# sub_board.net
KiCad netlist of a schematic drawn in EAGLE
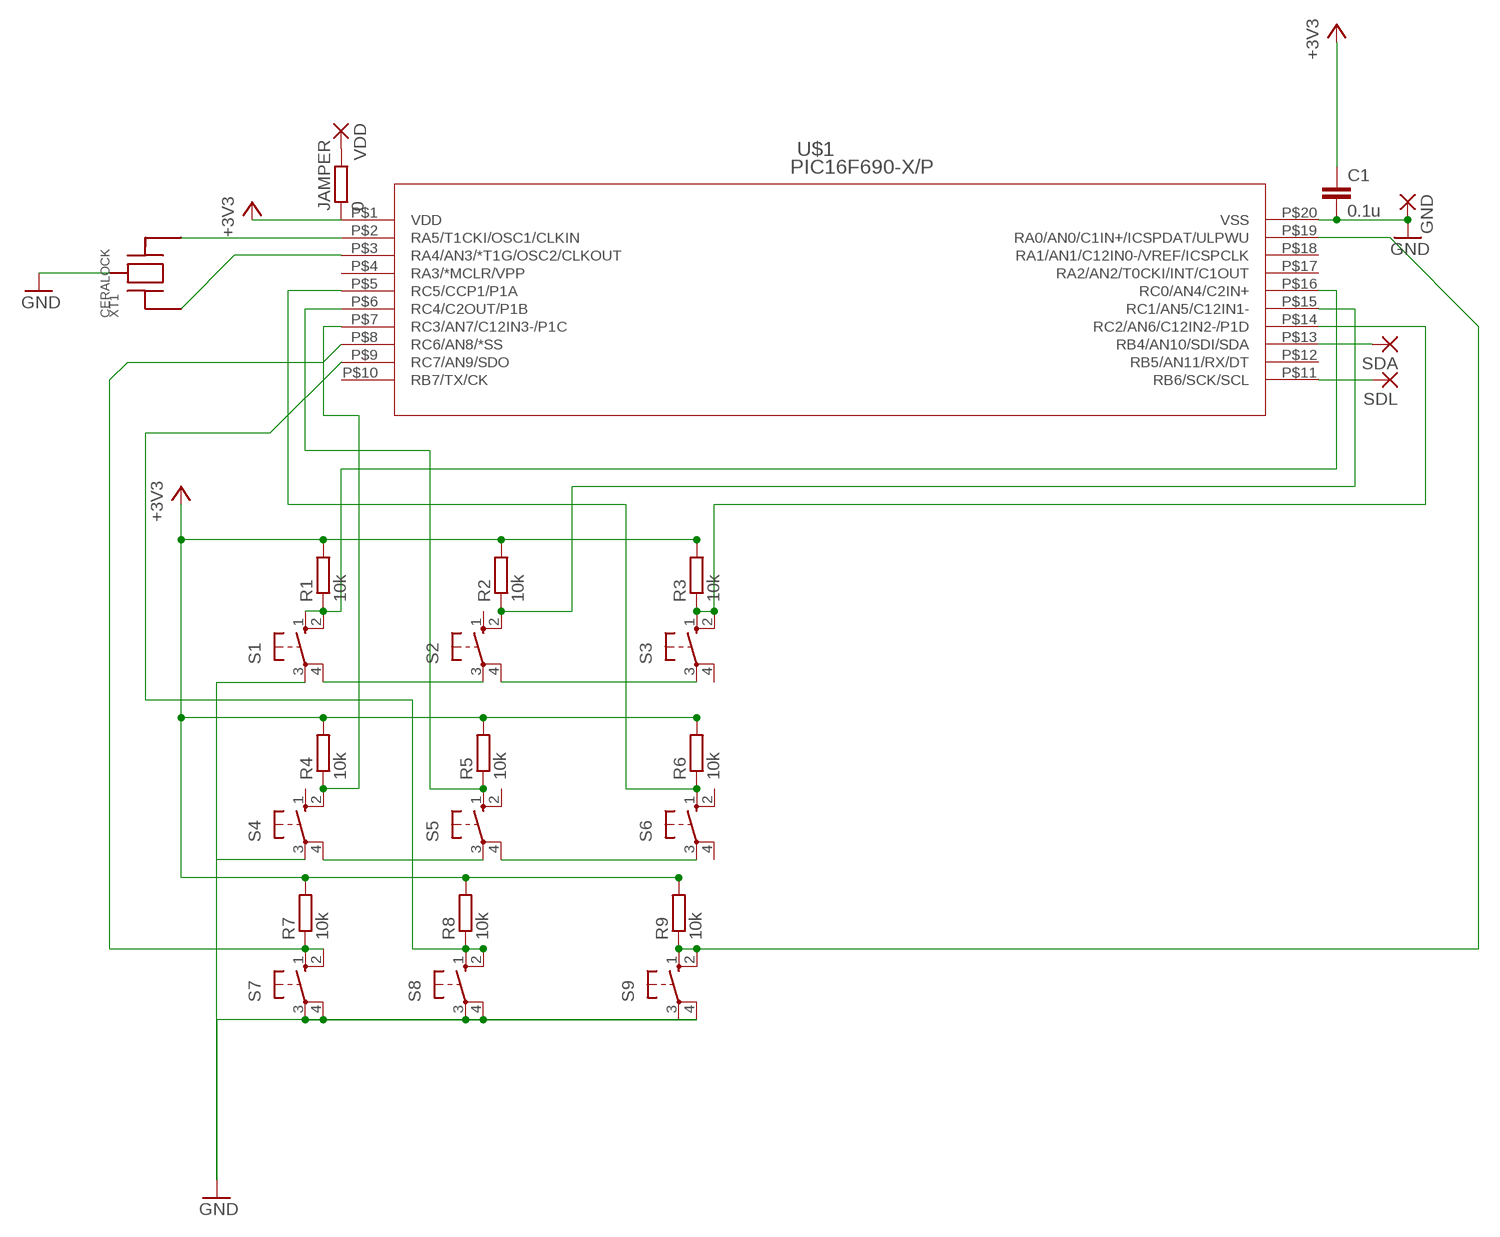
[diagram p0: schematic, sheet 1]

(export (version "E")
  (design (tool "Eeschema 10.0.6"))
  (components
    (comp (ref "C1")
      (value "0.1u")
      (footprint "eagle-import:C025-024X044")
      (libsource (lib "eagle-import") (part "C-EU025-024X044"))
    )
    (comp (ref "GND")
      (value "2,15/1,0")
      (footprint "eagle-import:2,15_1,0")
      (libsource (lib "eagle-import") (part "2,15/1,0"))
    )
    (comp (ref "JAMPER")
      (value "0")
      (footprint "eagle-import:0207_10")
      (libsource (lib "eagle-import") (part "R-EU_0207/10"))
    )
    (comp (ref "R1")
      (value "10k")
      (footprint "eagle-import:0204_7")
      (libsource (lib "eagle-import") (part "R-EU_0204/7"))
    )
    (comp (ref "R2")
      (value "10k")
      (footprint "eagle-import:0204_7")
      (libsource (lib "eagle-import") (part "R-EU_0204/7"))
    )
    (comp (ref "R3")
      (value "10k")
      (footprint "eagle-import:0204_7")
      (libsource (lib "eagle-import") (part "R-EU_0204/7"))
    )
    (comp (ref "R4")
      (value "10k")
      (footprint "eagle-import:0204_7")
      (libsource (lib "eagle-import") (part "R-EU_0204/7"))
    )
    (comp (ref "R5")
      (value "10k")
      (footprint "eagle-import:0204_7")
      (libsource (lib "eagle-import") (part "R-EU_0204/7"))
    )
    (comp (ref "R6")
      (value "10k")
      (footprint "eagle-import:0204_7")
      (libsource (lib "eagle-import") (part "R-EU_0204/7"))
    )
    (comp (ref "R7")
      (value "10k")
      (footprint "eagle-import:0204_7")
      (libsource (lib "eagle-import") (part "R-EU_0204/7"))
    )
    (comp (ref "R8")
      (value "10k")
      (footprint "eagle-import:0204_7")
      (libsource (lib "eagle-import") (part "R-EU_0204/7"))
    )
    (comp (ref "R9")
      (value "10k")
      (footprint "eagle-import:0204_7")
      (libsource (lib "eagle-import") (part "R-EU_0204/7"))
    )
    (comp (ref "S1")
      (value "10-XX")
      (footprint "eagle-import:B3F-10XX")
      (fields (field (name "MPN") "B3F-1000"))
      (libsource (lib "eagle-import") (part "10-XX"))
    )
    (comp (ref "S2")
      (value "10-XX")
      (footprint "eagle-import:B3F-10XX")
      (fields (field (name "MPN") "B3F-1000"))
      (libsource (lib "eagle-import") (part "10-XX"))
    )
    (comp (ref "S3")
      (value "10-XX")
      (footprint "eagle-import:B3F-10XX")
      (fields (field (name "MPN") "B3F-1000"))
      (libsource (lib "eagle-import") (part "10-XX"))
    )
    (comp (ref "S4")
      (value "10-XX")
      (footprint "eagle-import:B3F-10XX")
      (fields (field (name "MPN") "B3F-1000"))
      (libsource (lib "eagle-import") (part "10-XX"))
    )
    (comp (ref "S5")
      (value "10-XX")
      (footprint "eagle-import:B3F-10XX")
      (fields (field (name "MPN") "B3F-1000"))
      (libsource (lib "eagle-import") (part "10-XX"))
    )
    (comp (ref "S6")
      (value "10-XX")
      (footprint "eagle-import:B3F-10XX")
      (fields (field (name "MPN") "B3F-1000"))
      (libsource (lib "eagle-import") (part "10-XX"))
    )
    (comp (ref "S7")
      (value "10-XX")
      (footprint "eagle-import:B3F-10XX")
      (fields (field (name "MPN") "B3F-1000"))
      (libsource (lib "eagle-import") (part "10-XX"))
    )
    (comp (ref "S8")
      (value "10-XX")
      (footprint "eagle-import:B3F-10XX")
      (fields (field (name "MPN") "B3F-1000"))
      (libsource (lib "eagle-import") (part "10-XX"))
    )
    (comp (ref "S9")
      (value "10-XX")
      (footprint "eagle-import:B3F-10XX")
      (fields (field (name "MPN") "B3F-1000"))
      (libsource (lib "eagle-import") (part "10-XX"))
    )
    (comp (ref "SDA")
      (value "2,15/1,0")
      (footprint "eagle-import:2,15_1,0")
      (libsource (lib "eagle-import") (part "2,15/1,0"))
    )
    (comp (ref "SDL")
      (value "2,15/1,0")
      (footprint "eagle-import:2,15_1,0")
      (libsource (lib "eagle-import") (part "2,15/1,0"))
    )
    (comp (ref "U$1")
      (value "PIC16F690-X/P")
      (footprint "eagle-import:PDIP20_300MC")
      (libsource (lib "eagle-import") (part "PIC16F690-X/P"))
    )
    (comp (ref "VDD")
      (value "2,15/1,0")
      (footprint "eagle-import:2,15_1,0")
      (libsource (lib "eagle-import") (part "2,15/1,0"))
    )
    (comp (ref "XT1")
      (value "CERALOCK")
      (footprint "eagle-import:CERALOCK")
      (libsource (lib "eagle-import") (part "CERALOCK"))
    )
  )
  (nets
    (net (code "1") (name "+3V3") (class "Default")
      (node (ref "C1") (pin "1") (pinfunction "1_1") (pintype "passive"))
      (node (ref "JAMPER") (pin "1") (pinfunction "1_1") (pintype "passive"))
      (node (ref "R1") (pin "2") (pinfunction "2_2") (pintype "passive"))
      (node (ref "R2") (pin "2") (pinfunction "2_2") (pintype "passive"))
      (node (ref "R3") (pin "2") (pinfunction "2_2") (pintype "passive"))
      (node (ref "R4") (pin "2") (pinfunction "2_2") (pintype "passive"))
      (node (ref "R5") (pin "2") (pinfunction "2_2") (pintype "passive"))
      (node (ref "R6") (pin "2") (pinfunction "2_2") (pintype "passive"))
      (node (ref "R7") (pin "2") (pinfunction "2_2") (pintype "passive"))
      (node (ref "R8") (pin "2") (pinfunction "2_2") (pintype "passive"))
      (node (ref "R9") (pin "2") (pinfunction "2_2") (pintype "passive"))
      (node (ref "U$1") (pin "P$1") (pinfunction "VDD_P$1") (pintype "passive"))
    )
    (net (code "2") (name "GND") (class "Default")
      (node (ref "C1") (pin "2") (pinfunction "2_2") (pintype "passive"))
      (node (ref "GND") (pin "1") (pinfunction "P_1") (pintype "passive"))
      (node (ref "S1") (pin "3") (pinfunction "P_3") (pintype "passive"))
      (node (ref "S4") (pin "3") (pinfunction "P_3") (pintype "passive"))
      (node (ref "S7") (pin "3") (pinfunction "P_3") (pintype "passive"))
      (node (ref "S7") (pin "4") (pinfunction "P1_4") (pintype "passive"))
      (node (ref "S8") (pin "3") (pinfunction "P_3") (pintype "passive"))
      (node (ref "S8") (pin "4") (pinfunction "P1_4") (pintype "passive"))
      (node (ref "S9") (pin "3") (pinfunction "P_3") (pintype "passive"))
      (node (ref "S9") (pin "4") (pinfunction "P1_4") (pintype "passive"))
      (node (ref "U$1") (pin "P$20") (pinfunction "VSS_P$20") (pintype "passive"))
      (node (ref "XT1") (pin "P$2") (pinfunction "2_P$2") (pintype "passive"))
    )
    (net (code "3") (name "Net-(S1-P1)") (class "Default")
      (node (ref "S1") (pin "4") (pinfunction "P1_4") (pintype "passive"))
      (node (ref "S2") (pin "3") (pinfunction "P_3") (pintype "passive"))
    )
    (net (code "4") (name "Net-(S1-S)") (class "Default")
      (node (ref "R1") (pin "1") (pinfunction "1_1") (pintype "passive"))
      (node (ref "S1") (pin "1") (pinfunction "S_1") (pintype "passive"))
      (node (ref "S1") (pin "2") (pinfunction "S1_2") (pintype "passive"))
      (node (ref "U$1") (pin "P$16") (pinfunction "RC0/AN4/C2IN+_P$16") (pintype "passive"))
    )
    (net (code "5") (name "Net-(S2-P1)") (class "Default")
      (node (ref "S2") (pin "4") (pinfunction "P1_4") (pintype "passive"))
      (node (ref "S3") (pin "3") (pinfunction "P_3") (pintype "passive"))
    )
    (net (code "6") (name "Net-(S2-S1)") (class "Default")
      (node (ref "R2") (pin "1") (pinfunction "1_1") (pintype "passive"))
      (node (ref "S2") (pin "2") (pinfunction "S1_2") (pintype "passive"))
      (node (ref "U$1") (pin "P$15") (pinfunction "RC1/AN5/C12IN1-_P$15") (pintype "passive"))
    )
    (net (code "7") (name "Net-(S3-S)") (class "Default")
      (node (ref "R3") (pin "1") (pinfunction "1_1") (pintype "passive"))
      (node (ref "S3") (pin "1") (pinfunction "S_1") (pintype "passive"))
      (node (ref "S3") (pin "2") (pinfunction "S1_2") (pintype "passive"))
      (node (ref "U$1") (pin "P$14") (pinfunction "RC2/AN6/C12IN2-/P1D_P$14") (pintype "passive"))
    )
    (net (code "8") (name "Net-(S4-P1)") (class "Default")
      (node (ref "S4") (pin "4") (pinfunction "P1_4") (pintype "passive"))
      (node (ref "S5") (pin "3") (pinfunction "P_3") (pintype "passive"))
    )
    (net (code "9") (name "Net-(S4-S1)") (class "Default")
      (node (ref "R4") (pin "1") (pinfunction "1_1") (pintype "passive"))
      (node (ref "S4") (pin "2") (pinfunction "S1_2") (pintype "passive"))
      (node (ref "U$1") (pin "P$7") (pinfunction "RC3/AN7/C12IN3-/P1C_P$7") (pintype "passive"))
    )
    (net (code "10") (name "Net-(S5-P1)") (class "Default")
      (node (ref "S5") (pin "4") (pinfunction "P1_4") (pintype "passive"))
      (node (ref "S6") (pin "3") (pinfunction "P_3") (pintype "passive"))
    )
    (net (code "11") (name "Net-(S5-S)") (class "Default")
      (node (ref "R5") (pin "1") (pinfunction "1_1") (pintype "passive"))
      (node (ref "S5") (pin "1") (pinfunction "S_1") (pintype "passive"))
      (node (ref "U$1") (pin "P$6") (pinfunction "RC4/C2OUT/P1B_P$6") (pintype "passive"))
    )
    (net (code "12") (name "Net-(S6-S)") (class "Default")
      (node (ref "R6") (pin "1") (pinfunction "1_1") (pintype "passive"))
      (node (ref "S6") (pin "1") (pinfunction "S_1") (pintype "passive"))
      (node (ref "U$1") (pin "P$5") (pinfunction "RC5/CCP1/P1A_P$5") (pintype "passive"))
    )
    (net (code "13") (name "Net-(S7-S)") (class "Default")
      (node (ref "R7") (pin "1") (pinfunction "1_1") (pintype "passive"))
      (node (ref "S7") (pin "1") (pinfunction "S_1") (pintype "passive"))
      (node (ref "S7") (pin "2") (pinfunction "S1_2") (pintype "passive"))
      (node (ref "U$1") (pin "P$8") (pinfunction "RC6/AN8/*SS_P$8") (pintype "passive"))
    )
    (net (code "14") (name "Net-(S8-S)") (class "Default")
      (node (ref "R8") (pin "1") (pinfunction "1_1") (pintype "passive"))
      (node (ref "S8") (pin "1") (pinfunction "S_1") (pintype "passive"))
      (node (ref "S8") (pin "2") (pinfunction "S1_2") (pintype "passive"))
      (node (ref "U$1") (pin "P$9") (pinfunction "RC7/AN9/SDO_P$9") (pintype "passive"))
    )
    (net (code "15") (name "Net-(S9-S)") (class "Default")
      (node (ref "R9") (pin "1") (pinfunction "1_1") (pintype "passive"))
      (node (ref "S9") (pin "1") (pinfunction "S_1") (pintype "passive"))
      (node (ref "S9") (pin "2") (pinfunction "S1_2") (pintype "passive"))
      (node (ref "U$1") (pin "P$19") (pinfunction "RA0/AN0/C1IN+/ICSPDAT/ULPWU_P$19") (pintype "passive"))
    )
    (net (code "16") (name "Net-(SDA-P)") (class "Default")
      (node (ref "SDA") (pin "1") (pinfunction "P_1") (pintype "passive"))
      (node (ref "U$1") (pin "P$13") (pinfunction "RB4/AN10/SDI/SDA_P$13") (pintype "passive"))
    )
    (net (code "17") (name "Net-(SDL-P)") (class "Default")
      (node (ref "SDL") (pin "1") (pinfunction "P_1") (pintype "passive"))
      (node (ref "U$1") (pin "P$11") (pinfunction "RB6/SCK/SCL_P$11") (pintype "passive"))
    )
    (net (code "18") (name "Net-(U$1-RA4{slash}AN3{slash}*T1G{slash}OSC2{slash}CLKOUT)") (class "Default")
      (node (ref "U$1") (pin "P$3") (pinfunction "RA4/AN3/*T1G/OSC2/CLKOUT_P$3") (pintype "passive"))
      (node (ref "XT1") (pin "P$1") (pinfunction "1_P$1") (pintype "passive"))
    )
    (net (code "19") (name "Net-(U$1-RA5{slash}T1CKI{slash}OSC1{slash}CLKIN)") (class "Default")
      (node (ref "U$1") (pin "P$2") (pinfunction "RA5/T1CKI/OSC1/CLKIN_P$2") (pintype "passive"))
      (node (ref "XT1") (pin "P$3") (pinfunction "3_P$3") (pintype "passive"))
    )
    (net (code "20") (name "Net-(VDD-P)") (class "Default")
      (node (ref "JAMPER") (pin "2") (pinfunction "2_2") (pintype "passive"))
      (node (ref "VDD") (pin "1") (pinfunction "P_1") (pintype "passive"))
    )
    (net (code "21") (name "unconnected-(S2-S-Pad1)") (class "Default")
      (node (ref "S2") (pin "1") (pinfunction "S_1") (pintype "passive"))
    )
    (net (code "22") (name "unconnected-(S3-P1-Pad4)") (class "Default")
      (node (ref "S3") (pin "4") (pinfunction "P1_4") (pintype "passive"))
    )
    (net (code "23") (name "unconnected-(S4-S-Pad1)") (class "Default")
      (node (ref "S4") (pin "1") (pinfunction "S_1") (pintype "passive"))
    )
    (net (code "24") (name "unconnected-(S5-S1-Pad2)") (class "Default")
      (node (ref "S5") (pin "2") (pinfunction "S1_2") (pintype "passive"))
    )
    (net (code "25") (name "unconnected-(S6-P1-Pad4)") (class "Default")
      (node (ref "S6") (pin "4") (pinfunction "P1_4") (pintype "passive"))
    )
    (net (code "26") (name "unconnected-(S6-S1-Pad2)") (class "Default")
      (node (ref "S6") (pin "2") (pinfunction "S1_2") (pintype "passive"))
    )
    (net (code "27") (name "unconnected-(U$1-RA1{slash}AN1{slash}C12IN0-{slash}VREF{slash}ICSPCLK-PadP$18)") (class "Default")
      (node (ref "U$1") (pin "P$18") (pinfunction "RA1/AN1/C12IN0-/VREF/ICSPCLK_P$18") (pintype "passive"))
    )
    (net (code "28") (name "unconnected-(U$1-RA2{slash}AN2{slash}T0CKI{slash}INT{slash}C1OUT-PadP$17)") (class "Default")
      (node (ref "U$1") (pin "P$17") (pinfunction "RA2/AN2/T0CKI/INT/C1OUT_P$17") (pintype "passive"))
    )
    (net (code "29") (name "unconnected-(U$1-RA3{slash}*MCLR{slash}VPP-PadP$4)") (class "Default")
      (node (ref "U$1") (pin "P$4") (pinfunction "RA3/*MCLR/VPP_P$4") (pintype "passive"))
    )
    (net (code "30") (name "unconnected-(U$1-RB5{slash}AN11{slash}RX{slash}DT-PadP$12)") (class "Default")
      (node (ref "U$1") (pin "P$12") (pinfunction "RB5/AN11/RX/DT_P$12") (pintype "passive"))
    )
    (net (code "31") (name "unconnected-(U$1-RB7{slash}TX{slash}CK-PadP$10)") (class "Default")
      (node (ref "U$1") (pin "P$10") (pinfunction "RB7/TX/CK_P$10") (pintype "passive"))
    )
  )
)
